# lcd13264-shield.net
KiCad netlist of a schematic drawn in EAGLE
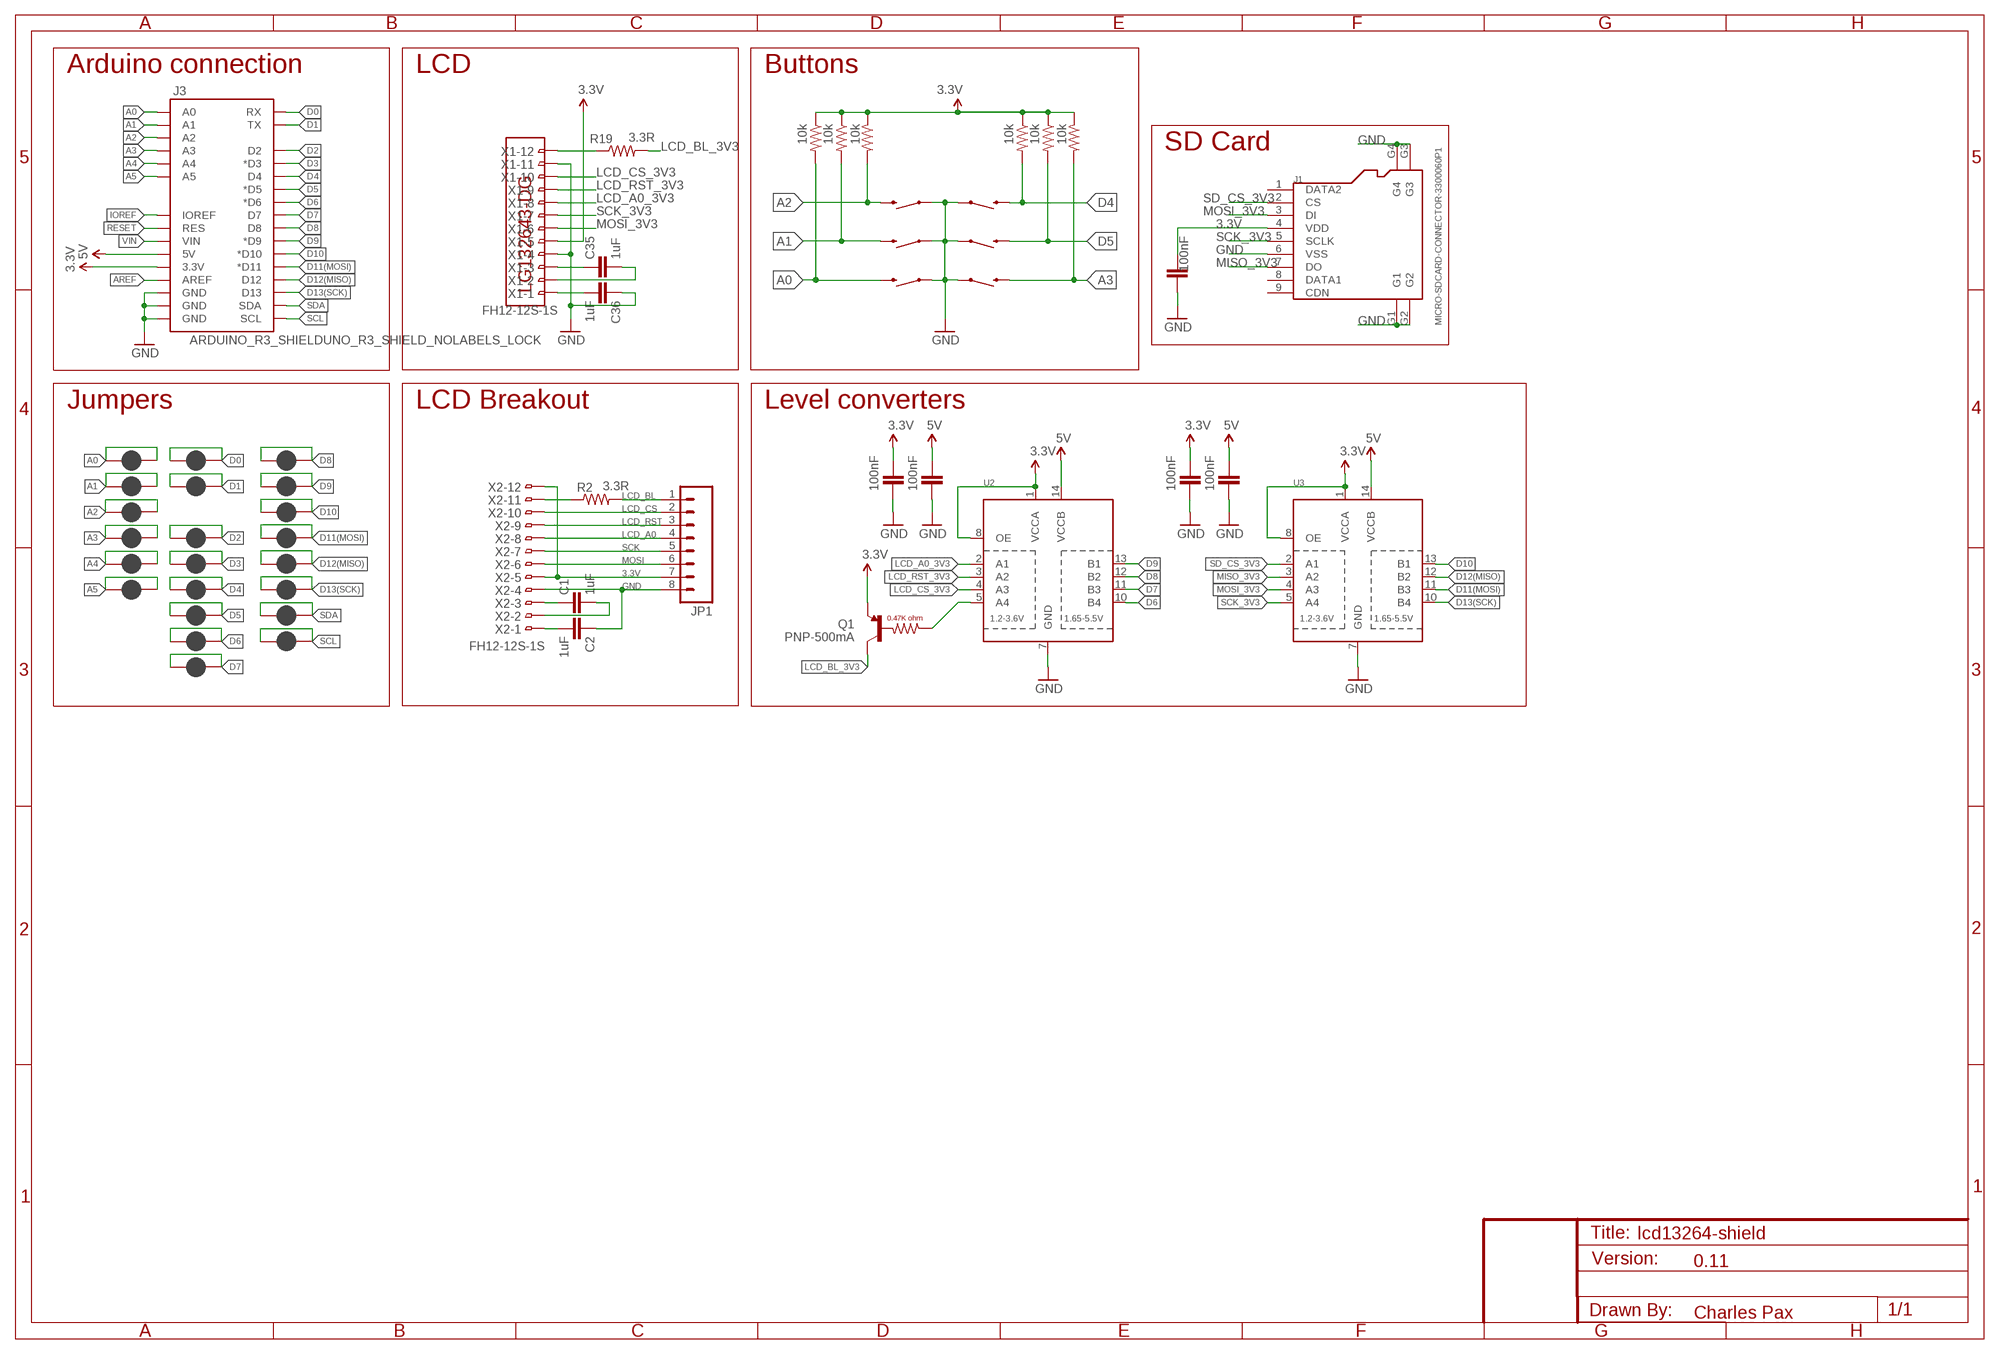
[diagram p0: schematic, sheet 1]

(export (version "E")
  (design (tool "Eeschema 10.0.6"))
  (components
    (comp (ref "C1")
      (value "1uF")
      (footprint "eagle-import:SPARKFUN-CAPACITORS_1206")
      (fields (field (name "MPN") "LMK107B7105KA-T"))
      (libsource (lib "eagle-import") (part "SPARKFUN-CAPACITORS_CAP1206"))
    )
    (comp (ref "C2")
      (value "1uF")
      (footprint "eagle-import:SPARKFUN-CAPACITORS_1206")
      (fields (field (name "MPN") "LMK107B7105KA-T"))
      (libsource (lib "eagle-import") (part "SPARKFUN-CAPACITORS_CAP1206"))
    )
    (comp (ref "C3")
      (value "100nF")
      (footprint "eagle-import:SPARKFUN-CAPACITORS_1206")
      (fields (field (name "MPN") "CL10B104KO8NNNC"))
      (libsource (lib "eagle-import") (part "SPARKFUN-CAPACITORS_CAP1206"))
    )
    (comp (ref "C4")
      (value "100nF")
      (footprint "eagle-import:SPARKFUN-CAPACITORS_1206")
      (fields (field (name "MPN") "CL10B104KO8NNNC"))
      (libsource (lib "eagle-import") (part "SPARKFUN-CAPACITORS_CAP1206"))
    )
    (comp (ref "C5")
      (value "100nF")
      (footprint "eagle-import:SPARKFUN-CAPACITORS_1206")
      (fields (field (name "MPN") "CL10B104KO8NNNC"))
      (libsource (lib "eagle-import") (part "SPARKFUN-CAPACITORS_CAP1206"))
    )
    (comp (ref "C6")
      (value "100nF")
      (footprint "eagle-import:SPARKFUN-CAPACITORS_1206")
      (fields (field (name "MPN") "CL10B104KO8NNNC"))
      (libsource (lib "eagle-import") (part "SPARKFUN-CAPACITORS_CAP1206"))
    )
    (comp (ref "C21")
      (value "100nF")
      (footprint "eagle-import:SPARKFUN-CAPACITORS_1206")
      (fields (field (name "MPN") "CL10B104KO8NNNC"))
      (libsource (lib "eagle-import") (part "SPARKFUN-CAPACITORS_CAP1206"))
    )
    (comp (ref "C35")
      (value "1uF")
      (footprint "eagle-import:SPARKFUN-CAPACITORS_1206")
      (fields (field (name "MPN") "LMK107B7105KA-T"))
      (libsource (lib "eagle-import") (part "SPARKFUN-CAPACITORS_CAP1206"))
    )
    (comp (ref "C36")
      (value "1uF")
      (footprint "eagle-import:SPARKFUN-CAPACITORS_1206")
      (fields (field (name "MPN") "LMK107B7105KA-T"))
      (libsource (lib "eagle-import") (part "SPARKFUN-CAPACITORS_CAP1206"))
    )
    (comp (ref "J1")
      (value "MICRO-SDCARD-CONNECTOR-3300060P1")
      (footprint "eagle-import:9P-SMD-W-RING")
      (libsource (lib "eagle-import") (part "MICRO-SDCARD-CONNECTOR-3300060P1"))
    )
    (comp (ref "J3")
      (value "ARDUINO_R3_SHIELDUNO_R3_SHIELD_NOLABELS_LOCK")
      (footprint "eagle-import:UNO_R3_SHIELD_NOLABELS_LOCK")
      (libsource (lib "eagle-import") (part "ARDUINO_R3_SHIELDUNO_R3_SHIELD_NOLABELS_LOCK"))
    )
    (comp (ref "JP1")
      (value "M08")
      (footprint "eagle-import:1X08_ROUND")
      (libsource (lib "eagle-import") (part "M08"))
    )
    (comp (ref "Q1")
      (value "PNP-500mA")
      (footprint "eagle-import:SOT23-3")
      (libsource (lib "eagle-import") (part "TRANSISTOR-PNP-DDTB142TC"))
    )
    (comp (ref "R1")
      (value "10k")
      (footprint "eagle-import:SPARKFUN-RESISTORS_1206")
      (fields (field (name "MPN") "RC1608J103CS"))
      (libsource (lib "eagle-import") (part "SPARKFUN-RESISTORS_RESISTOR1206"))
    )
    (comp (ref "R2")
      (value "3.3R")
      (footprint "eagle-import:SPARKFUN-RESISTORS_1206")
      (libsource (lib "eagle-import") (part "SPARKFUN-RESISTORS_RESISTOR1206"))
    )
    (comp (ref "R8")
      (value "10k")
      (footprint "eagle-import:SPARKFUN-RESISTORS_1206")
      (fields (field (name "MPN") "RC1608J103CS"))
      (libsource (lib "eagle-import") (part "SPARKFUN-RESISTORS_RESISTOR1206"))
    )
    (comp (ref "R11")
      (value "10k")
      (footprint "eagle-import:SPARKFUN-RESISTORS_1206")
      (fields (field (name "MPN") "RC1608J103CS"))
      (libsource (lib "eagle-import") (part "SPARKFUN-RESISTORS_RESISTOR1206"))
    )
    (comp (ref "R12")
      (value "10k")
      (footprint "eagle-import:SPARKFUN-RESISTORS_1206")
      (fields (field (name "MPN") "RC1608J103CS"))
      (libsource (lib "eagle-import") (part "SPARKFUN-RESISTORS_RESISTOR1206"))
    )
    (comp (ref "R15")
      (value "10k")
      (footprint "eagle-import:SPARKFUN-RESISTORS_1206")
      (fields (field (name "MPN") "RC1608J103CS"))
      (libsource (lib "eagle-import") (part "SPARKFUN-RESISTORS_RESISTOR1206"))
    )
    (comp (ref "R16")
      (value "10k")
      (footprint "eagle-import:SPARKFUN-RESISTORS_1206")
      (fields (field (name "MPN") "RC1608J103CS"))
      (libsource (lib "eagle-import") (part "SPARKFUN-RESISTORS_RESISTOR1206"))
    )
    (comp (ref "R19")
      (value "3.3R")
      (footprint "eagle-import:SPARKFUN-RESISTORS_1206")
      (libsource (lib "eagle-import") (part "SPARKFUN-RESISTORS_RESISTOR1206"))
    )
    (comp (ref "S1")
      (value "SWITCH-MOMENTARY-2SMD")
      (footprint "eagle-import:TACTILE_SWITCH_SMD")
      (libsource (lib "eagle-import") (part "SWITCH-MOMENTARY-2SMD"))
    )
    (comp (ref "S2")
      (value "SWITCH-MOMENTARY-2SMD")
      (footprint "eagle-import:TACTILE_SWITCH_SMD")
      (libsource (lib "eagle-import") (part "SWITCH-MOMENTARY-2SMD"))
    )
    (comp (ref "S3")
      (value "SWITCH-MOMENTARY-2SMD")
      (footprint "eagle-import:TACTILE_SWITCH_SMD")
      (libsource (lib "eagle-import") (part "SWITCH-MOMENTARY-2SMD"))
    )
    (comp (ref "S4")
      (value "SWITCH-MOMENTARY-2SMD")
      (footprint "eagle-import:TACTILE_SWITCH_SMD")
      (libsource (lib "eagle-import") (part "SWITCH-MOMENTARY-2SMD"))
    )
    (comp (ref "S5")
      (value "SWITCH-MOMENTARY-2SMD")
      (footprint "eagle-import:TACTILE_SWITCH_SMD")
      (libsource (lib "eagle-import") (part "SWITCH-MOMENTARY-2SMD"))
    )
    (comp (ref "S6")
      (value "SWITCH-MOMENTARY-2SMD")
      (footprint "eagle-import:TACTILE_SWITCH_SMD")
      (libsource (lib "eagle-import") (part "SWITCH-MOMENTARY-2SMD"))
    )
    (comp (ref "SJ1")
      (value "JUMPER-PAD-2-NC_BY_PASTE")
      (footprint "eagle-import:PAD-JUMPER-2-NC_BY_PASTE_YES_SILK")
      (libsource (lib "eagle-import") (part "JUMPER-PAD-2-NC_BY_PASTE"))
    )
    (comp (ref "SJ2")
      (value "JUMPER-PAD-2-NC_BY_PASTE")
      (footprint "eagle-import:PAD-JUMPER-2-NC_BY_PASTE_YES_SILK")
      (libsource (lib "eagle-import") (part "JUMPER-PAD-2-NC_BY_PASTE"))
    )
    (comp (ref "SJ3")
      (value "JUMPER-PAD-2-NC_BY_PASTE")
      (footprint "eagle-import:PAD-JUMPER-2-NC_BY_PASTE_YES_SILK")
      (libsource (lib "eagle-import") (part "JUMPER-PAD-2-NC_BY_PASTE"))
    )
    (comp (ref "SJ4")
      (value "JUMPER-PAD-2-NC_BY_PASTE")
      (footprint "eagle-import:PAD-JUMPER-2-NC_BY_PASTE_YES_SILK")
      (libsource (lib "eagle-import") (part "JUMPER-PAD-2-NC_BY_PASTE"))
    )
    (comp (ref "SJ5")
      (value "JUMPER-PAD-2-NC_BY_PASTE")
      (footprint "eagle-import:PAD-JUMPER-2-NC_BY_PASTE_YES_SILK")
      (libsource (lib "eagle-import") (part "JUMPER-PAD-2-NC_BY_PASTE"))
    )
    (comp (ref "SJ6")
      (value "JUMPER-PAD-2-NC_BY_PASTE")
      (footprint "eagle-import:PAD-JUMPER-2-NC_BY_PASTE_YES_SILK")
      (libsource (lib "eagle-import") (part "JUMPER-PAD-2-NC_BY_PASTE"))
    )
    (comp (ref "SJ7")
      (value "JUMPER-PAD-2-NC_BY_PASTE")
      (footprint "eagle-import:PAD-JUMPER-2-NC_BY_PASTE_YES_SILK")
      (libsource (lib "eagle-import") (part "JUMPER-PAD-2-NC_BY_PASTE"))
    )
    (comp (ref "SJ8")
      (value "JUMPER-PAD-2-NC_BY_PASTE")
      (footprint "eagle-import:PAD-JUMPER-2-NC_BY_PASTE_YES_SILK")
      (libsource (lib "eagle-import") (part "JUMPER-PAD-2-NC_BY_PASTE"))
    )
    (comp (ref "SJ9")
      (value "JUMPER-PAD-2-NC_BY_PASTE")
      (footprint "eagle-import:PAD-JUMPER-2-NC_BY_PASTE_YES_SILK")
      (libsource (lib "eagle-import") (part "JUMPER-PAD-2-NC_BY_PASTE"))
    )
    (comp (ref "SJ10")
      (value "JUMPER-PAD-2-NC_BY_PASTE")
      (footprint "eagle-import:PAD-JUMPER-2-NC_BY_PASTE_YES_SILK")
      (libsource (lib "eagle-import") (part "JUMPER-PAD-2-NC_BY_PASTE"))
    )
    (comp (ref "SJ11")
      (value "JUMPER-PAD-2-NC_BY_PASTE")
      (footprint "eagle-import:PAD-JUMPER-2-NC_BY_PASTE_YES_SILK")
      (libsource (lib "eagle-import") (part "JUMPER-PAD-2-NC_BY_PASTE"))
    )
    (comp (ref "SJ12")
      (value "JUMPER-PAD-2-NC_BY_PASTE")
      (footprint "eagle-import:PAD-JUMPER-2-NC_BY_PASTE_YES_SILK")
      (libsource (lib "eagle-import") (part "JUMPER-PAD-2-NC_BY_PASTE"))
    )
    (comp (ref "SJ13")
      (value "JUMPER-PAD-2-NC_BY_PASTE")
      (footprint "eagle-import:PAD-JUMPER-2-NC_BY_PASTE_YES_SILK")
      (libsource (lib "eagle-import") (part "JUMPER-PAD-2-NC_BY_PASTE"))
    )
    (comp (ref "SJ14")
      (value "JUMPER-PAD-2-NC_BY_PASTE")
      (footprint "eagle-import:PAD-JUMPER-2-NC_BY_PASTE_YES_SILK")
      (libsource (lib "eagle-import") (part "JUMPER-PAD-2-NC_BY_PASTE"))
    )
    (comp (ref "SJ19")
      (value "JUMPER-PAD-2-NC_BY_PASTE")
      (footprint "eagle-import:PAD-JUMPER-2-NC_BY_PASTE_YES_SILK")
      (libsource (lib "eagle-import") (part "JUMPER-PAD-2-NC_BY_PASTE"))
    )
    (comp (ref "SJ20")
      (value "JUMPER-PAD-2-NC_BY_PASTE")
      (footprint "eagle-import:PAD-JUMPER-2-NC_BY_PASTE_YES_SILK")
      (libsource (lib "eagle-import") (part "JUMPER-PAD-2-NC_BY_PASTE"))
    )
    (comp (ref "SJ21")
      (value "JUMPER-PAD-2-NC_BY_PASTE")
      (footprint "eagle-import:PAD-JUMPER-2-NC_BY_PASTE_YES_SILK")
      (libsource (lib "eagle-import") (part "JUMPER-PAD-2-NC_BY_PASTE"))
    )
    (comp (ref "SJ22")
      (value "JUMPER-PAD-2-NC_BY_PASTE")
      (footprint "eagle-import:PAD-JUMPER-2-NC_BY_PASTE_YES_SILK")
      (libsource (lib "eagle-import") (part "JUMPER-PAD-2-NC_BY_PASTE"))
    )
    (comp (ref "SJ23")
      (value "JUMPER-PAD-2-NC_BY_PASTE")
      (footprint "eagle-import:PAD-JUMPER-2-NC_BY_PASTE_YES_SILK")
      (libsource (lib "eagle-import") (part "JUMPER-PAD-2-NC_BY_PASTE"))
    )
    (comp (ref "SJ24")
      (value "JUMPER-PAD-2-NC_BY_PASTE")
      (footprint "eagle-import:PAD-JUMPER-2-NC_BY_PASTE_YES_SILK")
      (libsource (lib "eagle-import") (part "JUMPER-PAD-2-NC_BY_PASTE"))
    )
    (comp (ref "SJ25")
      (value "JUMPER-PAD-2-NC_BY_PASTE")
      (footprint "eagle-import:PAD-JUMPER-2-NC_BY_PASTE_YES_SILK")
      (libsource (lib "eagle-import") (part "JUMPER-PAD-2-NC_BY_PASTE"))
    )
    (comp (ref "SJ26")
      (value "JUMPER-PAD-2-NC_BY_PASTE")
      (footprint "eagle-import:PAD-JUMPER-2-NC_BY_PASTE_YES_SILK")
      (libsource (lib "eagle-import") (part "JUMPER-PAD-2-NC_BY_PASTE"))
    )
    (comp (ref "U$5")
      (value "LG132643-DG")
      (footprint "eagle-import:LG132643-DG")
      (fields (field (name "MPN") "LG132643-DW"))
      (libsource (lib "eagle-import") (part "LG132643-DG"))
    )
    (comp (ref "U2")
      (value "TXB0104PWRSOIC14")
      (footprint "eagle-import:SO14")
      (libsource (lib "eagle-import") (part "TXB0104PWRSOIC14"))
    )
    (comp (ref "U3")
      (value "TXB0104PWRSOIC14")
      (footprint "eagle-import:SO14")
      (libsource (lib "eagle-import") (part "TXB0104PWRSOIC14"))
    )
    (comp (ref "X1")
      (value "FH12-12S-1S")
      (footprint "eagle-import:FH12-12S-1SH")
      (libsource (lib "eagle-import") (part "FH12-12S-1S"))
    )
    (comp (ref "X2")
      (value "FH12-12S-1S")
      (footprint "eagle-import:FH12-12S-1SH")
      (libsource (lib "eagle-import") (part "FH12-12S-1S"))
    )
  )
  (nets
    (net (code "1") (name "3.3V") (class "Default")
      (node (ref "C21") (pin "2") (pinfunction "2_2") (pintype "passive"))
      (node (ref "C3") (pin "2") (pinfunction "2_2") (pintype "passive"))
      (node (ref "C5") (pin "2") (pinfunction "2_2") (pintype "passive"))
      (node (ref "J1") (pin "4") (pinfunction "VDD_4") (pintype "bidirectional"))
      (node (ref "J3") (pin "3.3V") (pinfunction "3.3V_3.3V") (pintype "bidirectional"))
      (node (ref "Q1") (pin "2") (pinfunction "E_2") (pintype "passive"))
      (node (ref "R1") (pin "1") (pinfunction "1_1") (pintype "passive"))
      (node (ref "R11") (pin "1") (pinfunction "1_1") (pintype "passive"))
      (node (ref "R12") (pin "1") (pinfunction "1_1") (pintype "passive"))
      (node (ref "R15") (pin "1") (pinfunction "1_1") (pintype "passive"))
      (node (ref "R16") (pin "1") (pinfunction "1_1") (pintype "passive"))
      (node (ref "R8") (pin "1") (pinfunction "1_1") (pintype "passive"))
      (node (ref "U2") (pin "1") (pinfunction "VCCA_1") (pintype "bidirectional"))
      (node (ref "U2") (pin "8") (pinfunction "OE_8") (pintype "bidirectional"))
      (node (ref "U3") (pin "1") (pinfunction "VCCA_1") (pintype "bidirectional"))
      (node (ref "U3") (pin "8") (pinfunction "OE_8") (pintype "bidirectional"))
      (node (ref "X1") (pin "5") (pinfunction "1_5") (pintype "passive"))
    )
    (net (code "2") (name "5V") (class "Default")
      (node (ref "C4") (pin "2") (pinfunction "2_2") (pintype "passive"))
      (node (ref "C6") (pin "2") (pinfunction "2_2") (pintype "passive"))
      (node (ref "J3") (pin "5V") (pinfunction "5V_5V") (pintype "bidirectional"))
      (node (ref "U2") (pin "14") (pinfunction "VCCB_14") (pintype "bidirectional"))
      (node (ref "U3") (pin "14") (pinfunction "VCCB_14") (pintype "bidirectional"))
    )
    (net (code "3") (name "A0") (class "Default")
      (node (ref "J3") (pin "A0") (pinfunction "A0_A0") (pintype "bidirectional"))
      (node (ref "R1") (pin "2") (pinfunction "2_2") (pintype "passive"))
      (node (ref "S6") (pin "3") (pinfunction "2_3") (pintype "passive"))
      (node (ref "SJ10") (pin "1") (pinfunction "1_1") (pintype "passive"))
      (node (ref "SJ10") (pin "2") (pinfunction "2_2") (pintype "passive"))
    )
    (net (code "4") (name "A1") (class "Default")
      (node (ref "J3") (pin "A1") (pinfunction "A1_A1") (pintype "bidirectional"))
      (node (ref "R16") (pin "2") (pinfunction "2_2") (pintype "passive"))
      (node (ref "S5") (pin "3") (pinfunction "2_3") (pintype "passive"))
      (node (ref "SJ7") (pin "1") (pinfunction "1_1") (pintype "passive"))
      (node (ref "SJ7") (pin "2") (pinfunction "2_2") (pintype "passive"))
    )
    (net (code "5") (name "A2") (class "Default")
      (node (ref "J3") (pin "A2") (pinfunction "A2_A2") (pintype "bidirectional"))
      (node (ref "R15") (pin "2") (pinfunction "2_2") (pintype "passive"))
      (node (ref "S4") (pin "3") (pinfunction "2_3") (pintype "passive"))
      (node (ref "SJ11") (pin "1") (pinfunction "1_1") (pintype "passive"))
      (node (ref "SJ11") (pin "2") (pinfunction "2_2") (pintype "passive"))
    )
    (net (code "6") (name "A3") (class "Default")
      (node (ref "J3") (pin "A3") (pinfunction "A3_A3") (pintype "bidirectional"))
      (node (ref "R12") (pin "2") (pinfunction "2_2") (pintype "passive"))
      (node (ref "S1") (pin "3") (pinfunction "2_3") (pintype "passive"))
      (node (ref "SJ12") (pin "1") (pinfunction "1_1") (pintype "passive"))
      (node (ref "SJ12") (pin "2") (pinfunction "2_2") (pintype "passive"))
    )
    (net (code "7") (name "A4") (class "Default")
      (node (ref "J3") (pin "A4") (pinfunction "A4_A4") (pintype "bidirectional"))
      (node (ref "SJ13") (pin "1") (pinfunction "1_1") (pintype "passive"))
      (node (ref "SJ13") (pin "2") (pinfunction "2_2") (pintype "passive"))
    )
    (net (code "8") (name "A5") (class "Default")
      (node (ref "J3") (pin "A5") (pinfunction "A5_A5") (pintype "bidirectional"))
      (node (ref "SJ14") (pin "1") (pinfunction "1_1") (pintype "passive"))
      (node (ref "SJ14") (pin "2") (pinfunction "2_2") (pintype "passive"))
    )
    (net (code "9") (name "AREF") (class "Default")
      (node (ref "J3") (pin "AREF") (pinfunction "AREF_AREF") (pintype "bidirectional"))
    )
    (net (code "10") (name "D0") (class "Default")
      (node (ref "J3") (pin "RX") (pinfunction "RX_RX") (pintype "bidirectional"))
      (node (ref "SJ8") (pin "1") (pinfunction "1_1") (pintype "passive"))
      (node (ref "SJ8") (pin "2") (pinfunction "2_2") (pintype "passive"))
    )
    (net (code "11") (name "D1") (class "Default")
      (node (ref "J3") (pin "TX") (pinfunction "TX_TX") (pintype "bidirectional"))
      (node (ref "SJ9") (pin "1") (pinfunction "1_1") (pintype "passive"))
      (node (ref "SJ9") (pin "2") (pinfunction "2_2") (pintype "passive"))
    )
    (net (code "12") (name "D2") (class "Default")
      (node (ref "J3") (pin "D2") (pinfunction "D2_D2") (pintype "bidirectional"))
      (node (ref "SJ3") (pin "1") (pinfunction "1_1") (pintype "passive"))
      (node (ref "SJ3") (pin "2") (pinfunction "2_2") (pintype "passive"))
    )
    (net (code "13") (name "D3") (class "Default")
      (node (ref "J3") (pin "D3") (pinfunction "*D3_D3") (pintype "bidirectional"))
      (node (ref "SJ4") (pin "1") (pinfunction "1_1") (pintype "passive"))
      (node (ref "SJ4") (pin "2") (pinfunction "2_2") (pintype "passive"))
    )
    (net (code "14") (name "D4") (class "Default")
      (node (ref "J3") (pin "D4") (pinfunction "D4_D4") (pintype "bidirectional"))
      (node (ref "R8") (pin "2") (pinfunction "2_2") (pintype "passive"))
      (node (ref "S3") (pin "3") (pinfunction "2_3") (pintype "passive"))
      (node (ref "SJ5") (pin "1") (pinfunction "1_1") (pintype "passive"))
      (node (ref "SJ5") (pin "2") (pinfunction "2_2") (pintype "passive"))
    )
    (net (code "15") (name "D5") (class "Default")
      (node (ref "J3") (pin "D5") (pinfunction "*D5_D5") (pintype "bidirectional"))
      (node (ref "R11") (pin "2") (pinfunction "2_2") (pintype "passive"))
      (node (ref "S2") (pin "3") (pinfunction "2_3") (pintype "passive"))
      (node (ref "SJ6") (pin "1") (pinfunction "1_1") (pintype "passive"))
      (node (ref "SJ6") (pin "2") (pinfunction "2_2") (pintype "passive"))
    )
    (net (code "16") (name "D6") (class "Default")
      (node (ref "J3") (pin "D6") (pinfunction "*D6_D6") (pintype "bidirectional"))
      (node (ref "SJ19") (pin "1") (pinfunction "1_1") (pintype "passive"))
      (node (ref "SJ19") (pin "2") (pinfunction "2_2") (pintype "passive"))
      (node (ref "U2") (pin "10") (pinfunction "B4_10") (pintype "bidirectional"))
    )
    (net (code "17") (name "D7") (class "Default")
      (node (ref "J3") (pin "D7") (pinfunction "D7_D7") (pintype "bidirectional"))
      (node (ref "SJ20") (pin "1") (pinfunction "1_1") (pintype "passive"))
      (node (ref "SJ20") (pin "2") (pinfunction "2_2") (pintype "passive"))
      (node (ref "U2") (pin "11") (pinfunction "B3_11") (pintype "bidirectional"))
    )
    (net (code "18") (name "D8") (class "Default")
      (node (ref "J3") (pin "D8") (pinfunction "D8_D8") (pintype "bidirectional"))
      (node (ref "SJ21") (pin "1") (pinfunction "1_1") (pintype "passive"))
      (node (ref "SJ21") (pin "2") (pinfunction "2_2") (pintype "passive"))
      (node (ref "U2") (pin "12") (pinfunction "B2_12") (pintype "bidirectional"))
    )
    (net (code "19") (name "D9") (class "Default")
      (node (ref "J3") (pin "D9") (pinfunction "*D9_D9") (pintype "bidirectional"))
      (node (ref "SJ22") (pin "1") (pinfunction "1_1") (pintype "passive"))
      (node (ref "SJ22") (pin "2") (pinfunction "2_2") (pintype "passive"))
      (node (ref "U2") (pin "13") (pinfunction "B1_13") (pintype "bidirectional"))
    )
    (net (code "20") (name "D10") (class "Default")
      (node (ref "J3") (pin "D10") (pinfunction "*D10_D10") (pintype "bidirectional"))
      (node (ref "SJ23") (pin "1") (pinfunction "1_1") (pintype "passive"))
      (node (ref "SJ23") (pin "2") (pinfunction "2_2") (pintype "passive"))
      (node (ref "U3") (pin "13") (pinfunction "B1_13") (pintype "bidirectional"))
    )
    (net (code "21") (name "D11(MOSI)") (class "Default")
      (node (ref "J3") (pin "D11") (pinfunction "*D11_D11") (pintype "bidirectional"))
      (node (ref "SJ24") (pin "1") (pinfunction "1_1") (pintype "passive"))
      (node (ref "SJ24") (pin "2") (pinfunction "2_2") (pintype "passive"))
      (node (ref "U3") (pin "11") (pinfunction "B3_11") (pintype "bidirectional"))
    )
    (net (code "22") (name "D12(MISO)") (class "Default")
      (node (ref "J3") (pin "D12") (pinfunction "D12_D12") (pintype "bidirectional"))
      (node (ref "SJ25") (pin "1") (pinfunction "1_1") (pintype "passive"))
      (node (ref "SJ25") (pin "2") (pinfunction "2_2") (pintype "passive"))
      (node (ref "U3") (pin "12") (pinfunction "B2_12") (pintype "bidirectional"))
    )
    (net (code "23") (name "D13(SCK)") (class "Default")
      (node (ref "J3") (pin "D13") (pinfunction "D13_D13") (pintype "bidirectional"))
      (node (ref "SJ26") (pin "1") (pinfunction "1_1") (pintype "passive"))
      (node (ref "SJ26") (pin "2") (pinfunction "2_2") (pintype "passive"))
      (node (ref "U3") (pin "10") (pinfunction "B4_10") (pintype "bidirectional"))
    )
    (net (code "24") (name "GND") (class "Default")
      (node (ref "C2") (pin "1") (pinfunction "1_1") (pintype "passive"))
      (node (ref "C21") (pin "1") (pinfunction "1_1") (pintype "passive"))
      (node (ref "C3") (pin "1") (pinfunction "1_1") (pintype "passive"))
      (node (ref "C36") (pin "1") (pinfunction "1_1") (pintype "passive"))
      (node (ref "C4") (pin "1") (pinfunction "1_1") (pintype "passive"))
      (node (ref "C5") (pin "1") (pinfunction "1_1") (pintype "passive"))
      (node (ref "C6") (pin "1") (pinfunction "1_1") (pintype "passive"))
      (node (ref "J1") (pin "6") (pinfunction "VSS_6") (pintype "bidirectional"))
      (node (ref "J1") (pin "G1") (pinfunction "G1_G1") (pintype "bidirectional"))
      (node (ref "J1") (pin "G2") (pinfunction "G2_G2") (pintype "bidirectional"))
      (node (ref "J1") (pin "G3") (pinfunction "G3_G3") (pintype "bidirectional"))
      (node (ref "J1") (pin "G4") (pinfunction "G4_G4") (pintype "bidirectional"))
      (node (ref "J3") (pin "GND@0") (pinfunction "GND_GND@0") (pintype "bidirectional"))
      (node (ref "J3") (pin "GND@1") (pinfunction "GND_GND@1") (pintype "bidirectional"))
      (node (ref "J3") (pin "GND@2") (pinfunction "GND_GND@2") (pintype "bidirectional"))
      (node (ref "JP1") (pin "8") (pinfunction "8_8") (pintype "passive"))
      (node (ref "S1") (pin "1") (pinfunction "1_1") (pintype "passive"))
      (node (ref "S2") (pin "1") (pinfunction "1_1") (pintype "passive"))
      (node (ref "S3") (pin "1") (pinfunction "1_1") (pintype "passive"))
      (node (ref "S4") (pin "1") (pinfunction "1_1") (pintype "passive"))
      (node (ref "S5") (pin "1") (pinfunction "1_1") (pintype "passive"))
      (node (ref "S6") (pin "1") (pinfunction "1_1") (pintype "passive"))
      (node (ref "U2") (pin "7") (pinfunction "GND_7") (pintype "bidirectional"))
      (node (ref "U3") (pin "7") (pinfunction "GND_7") (pintype "bidirectional"))
      (node (ref "X1") (pin "11") (pinfunction "1_11") (pintype "passive"))
      (node (ref "X1") (pin "4") (pinfunction "1_4") (pintype "passive"))
      (node (ref "X2") (pin "4") (pinfunction "1_4") (pintype "passive"))
    )
    (net (code "25") (name "IOREF") (class "Default")
      (node (ref "J3") (pin "IOREF") (pinfunction "IOREF_IOREF") (pintype "bidirectional"))
    )
    (net (code "26") (name "LCD_A0_3V3") (class "Default")
      (node (ref "U2") (pin "2") (pinfunction "A1_2") (pintype "bidirectional"))
      (node (ref "X1") (pin "8") (pinfunction "1_8") (pintype "passive"))
    )
    (net (code "27") (name "LCD_BL_3V3") (class "Default")
      (node (ref "Q1") (pin "3") (pinfunction "C_3") (pintype "passive"))
      (node (ref "R19") (pin "2") (pinfunction "2_2") (pintype "passive"))
    )
    (net (code "28") (name "LCD_CS_3V3") (class "Default")
      (node (ref "U2") (pin "4") (pinfunction "A3_4") (pintype "bidirectional"))
      (node (ref "X1") (pin "10") (pinfunction "1_10") (pintype "passive"))
    )
    (net (code "29") (name "LCD_RST_3V3") (class "Default")
      (node (ref "U2") (pin "3") (pinfunction "A2_3") (pintype "bidirectional"))
      (node (ref "X1") (pin "9") (pinfunction "1_9") (pintype "passive"))
    )
    (net (code "30") (name "MISO_3V3") (class "Default")
      (node (ref "J1") (pin "7") (pinfunction "DO_7") (pintype "bidirectional"))
      (node (ref "U3") (pin "3") (pinfunction "A2_3") (pintype "bidirectional"))
    )
    (net (code "31") (name "MOSI_3V3") (class "Default")
      (node (ref "J1") (pin "3") (pinfunction "DI_3") (pintype "bidirectional"))
      (node (ref "U3") (pin "4") (pinfunction "A3_4") (pintype "bidirectional"))
      (node (ref "X1") (pin "6") (pinfunction "1_6") (pintype "passive"))
    )
    (net (code "32") (name "Net-(C2-Pad2)") (class "Default")
      (node (ref "C2") (pin "2") (pinfunction "2_2") (pintype "passive"))
      (node (ref "X2") (pin "1") (pinfunction "1_1") (pintype "passive"))
    )
    (net (code "33") (name "Net-(C36-Pad2)") (class "Default")
      (node (ref "C36") (pin "2") (pinfunction "2_2") (pintype "passive"))
      (node (ref "X1") (pin "1") (pinfunction "1_1") (pintype "passive"))
    )
    (net (code "34") (name "Net-(JP1-Pad1)") (class "Default")
      (node (ref "JP1") (pin "1") (pinfunction "1_1") (pintype "passive"))
      (node (ref "R2") (pin "2") (pinfunction "2_2") (pintype "passive"))
    )
    (net (code "35") (name "Net-(Q1-B)") (class "Default")
      (node (ref "Q1") (pin "1") (pinfunction "B_1") (pintype "passive"))
      (node (ref "U2") (pin "5") (pinfunction "A4_5") (pintype "bidirectional"))
    )
    (net (code "36") (name "Net-(X1D-1)") (class "Default")
      (node (ref "R19") (pin "1") (pinfunction "1_1") (pintype "passive"))
      (node (ref "X1") (pin "12") (pinfunction "1_12") (pintype "passive"))
    )
    (net (code "37") (name "Net-(X1E-1)") (class "Default")
      (node (ref "C35") (pin "2") (pinfunction "2_2") (pintype "passive"))
      (node (ref "X1") (pin "2") (pinfunction "1_2") (pintype "passive"))
    )
    (net (code "38") (name "Net-(X1F-1)") (class "Default")
      (node (ref "C35") (pin "1") (pinfunction "1_1") (pintype "passive"))
      (node (ref "X1") (pin "3") (pinfunction "1_3") (pintype "passive"))
    )
    (net (code "39") (name "Net-(X2B-1)") (class "Default")
      (node (ref "JP1") (pin "2") (pinfunction "2_2") (pintype "passive"))
      (node (ref "X2") (pin "10") (pinfunction "1_10") (pintype "passive"))
    )
    (net (code "40") (name "Net-(X2C-1)") (class "Default")
      (node (ref "R2") (pin "1") (pinfunction "1_1") (pintype "passive"))
      (node (ref "X2") (pin "11") (pinfunction "1_11") (pintype "passive"))
    )
    (net (code "41") (name "Net-(X2D-1)") (class "Default")
      (node (ref "JP1") (pin "7") (pinfunction "7_7") (pintype "passive"))
      (node (ref "X2") (pin "12") (pinfunction "1_12") (pintype "passive"))
      (node (ref "X2") (pin "5") (pinfunction "1_5") (pintype "passive"))
    )
    (net (code "42") (name "Net-(X2E-1)") (class "Default")
      (node (ref "C1") (pin "2") (pinfunction "2_2") (pintype "passive"))
      (node (ref "X2") (pin "2") (pinfunction "1_2") (pintype "passive"))
    )
    (net (code "43") (name "Net-(X2F-1)") (class "Default")
      (node (ref "C1") (pin "1") (pinfunction "1_1") (pintype "passive"))
      (node (ref "X2") (pin "3") (pinfunction "1_3") (pintype "passive"))
    )
    (net (code "44") (name "Net-(X2I-1)") (class "Default")
      (node (ref "JP1") (pin "6") (pinfunction "6_6") (pintype "passive"))
      (node (ref "X2") (pin "6") (pinfunction "1_6") (pintype "passive"))
    )
    (net (code "45") (name "Net-(X2J-1)") (class "Default")
      (node (ref "JP1") (pin "5") (pinfunction "5_5") (pintype "passive"))
      (node (ref "X2") (pin "7") (pinfunction "1_7") (pintype "passive"))
    )
    (net (code "46") (name "Net-(X2K-1)") (class "Default")
      (node (ref "JP1") (pin "4") (pinfunction "4_4") (pintype "passive"))
      (node (ref "X2") (pin "8") (pinfunction "1_8") (pintype "passive"))
    )
    (net (code "47") (name "Net-(X2L-1)") (class "Default")
      (node (ref "JP1") (pin "3") (pinfunction "3_3") (pintype "passive"))
      (node (ref "X2") (pin "9") (pinfunction "1_9") (pintype "passive"))
    )
    (net (code "48") (name "RESET") (class "Default")
      (node (ref "J3") (pin "RES") (pinfunction "RES_RES") (pintype "bidirectional"))
    )
    (net (code "49") (name "SCK_3V3") (class "Default")
      (node (ref "J1") (pin "5") (pinfunction "SCLK_5") (pintype "bidirectional"))
      (node (ref "U3") (pin "5") (pinfunction "A4_5") (pintype "bidirectional"))
      (node (ref "X1") (pin "7") (pinfunction "1_7") (pintype "passive"))
    )
    (net (code "50") (name "SCL") (class "Default")
      (node (ref "J3") (pin "SCL") (pinfunction "SCL_SCL") (pintype "bidirectional"))
      (node (ref "SJ2") (pin "1") (pinfunction "1_1") (pintype "passive"))
      (node (ref "SJ2") (pin "2") (pinfunction "2_2") (pintype "passive"))
    )
    (net (code "51") (name "SDA") (class "Default")
      (node (ref "J3") (pin "SDA") (pinfunction "SDA_SDA") (pintype "bidirectional"))
      (node (ref "SJ1") (pin "1") (pinfunction "1_1") (pintype "passive"))
      (node (ref "SJ1") (pin "2") (pinfunction "2_2") (pintype "passive"))
    )
    (net (code "52") (name "SD_CS_3V3") (class "Default")
      (node (ref "J1") (pin "2") (pinfunction "CS_2") (pintype "bidirectional"))
      (node (ref "U3") (pin "2") (pinfunction "A1_2") (pintype "bidirectional"))
    )
    (net (code "53") (name "VIN") (class "Default")
      (node (ref "J3") (pin "VIN") (pinfunction "VIN_VIN") (pintype "bidirectional"))
    )
    (net (code "54") (name "unconnected-(J1-CDN-Pad9)") (class "Default")
      (node (ref "J1") (pin "9") (pinfunction "CDN_9") (pintype "bidirectional"))
    )
    (net (code "55") (name "unconnected-(J1-DATA1-Pad8)") (class "Default")
      (node (ref "J1") (pin "8") (pinfunction "DATA1_8") (pintype "bidirectional"))
    )
    (net (code "56") (name "unconnected-(J1-DATA2-Pad1)") (class "Default")
      (node (ref "J1") (pin "1") (pinfunction "DATA2_1") (pintype "bidirectional"))
    )
  )
)
